# 6packRev1B.net
KiCad netlist of a schematic drawn in EAGLE
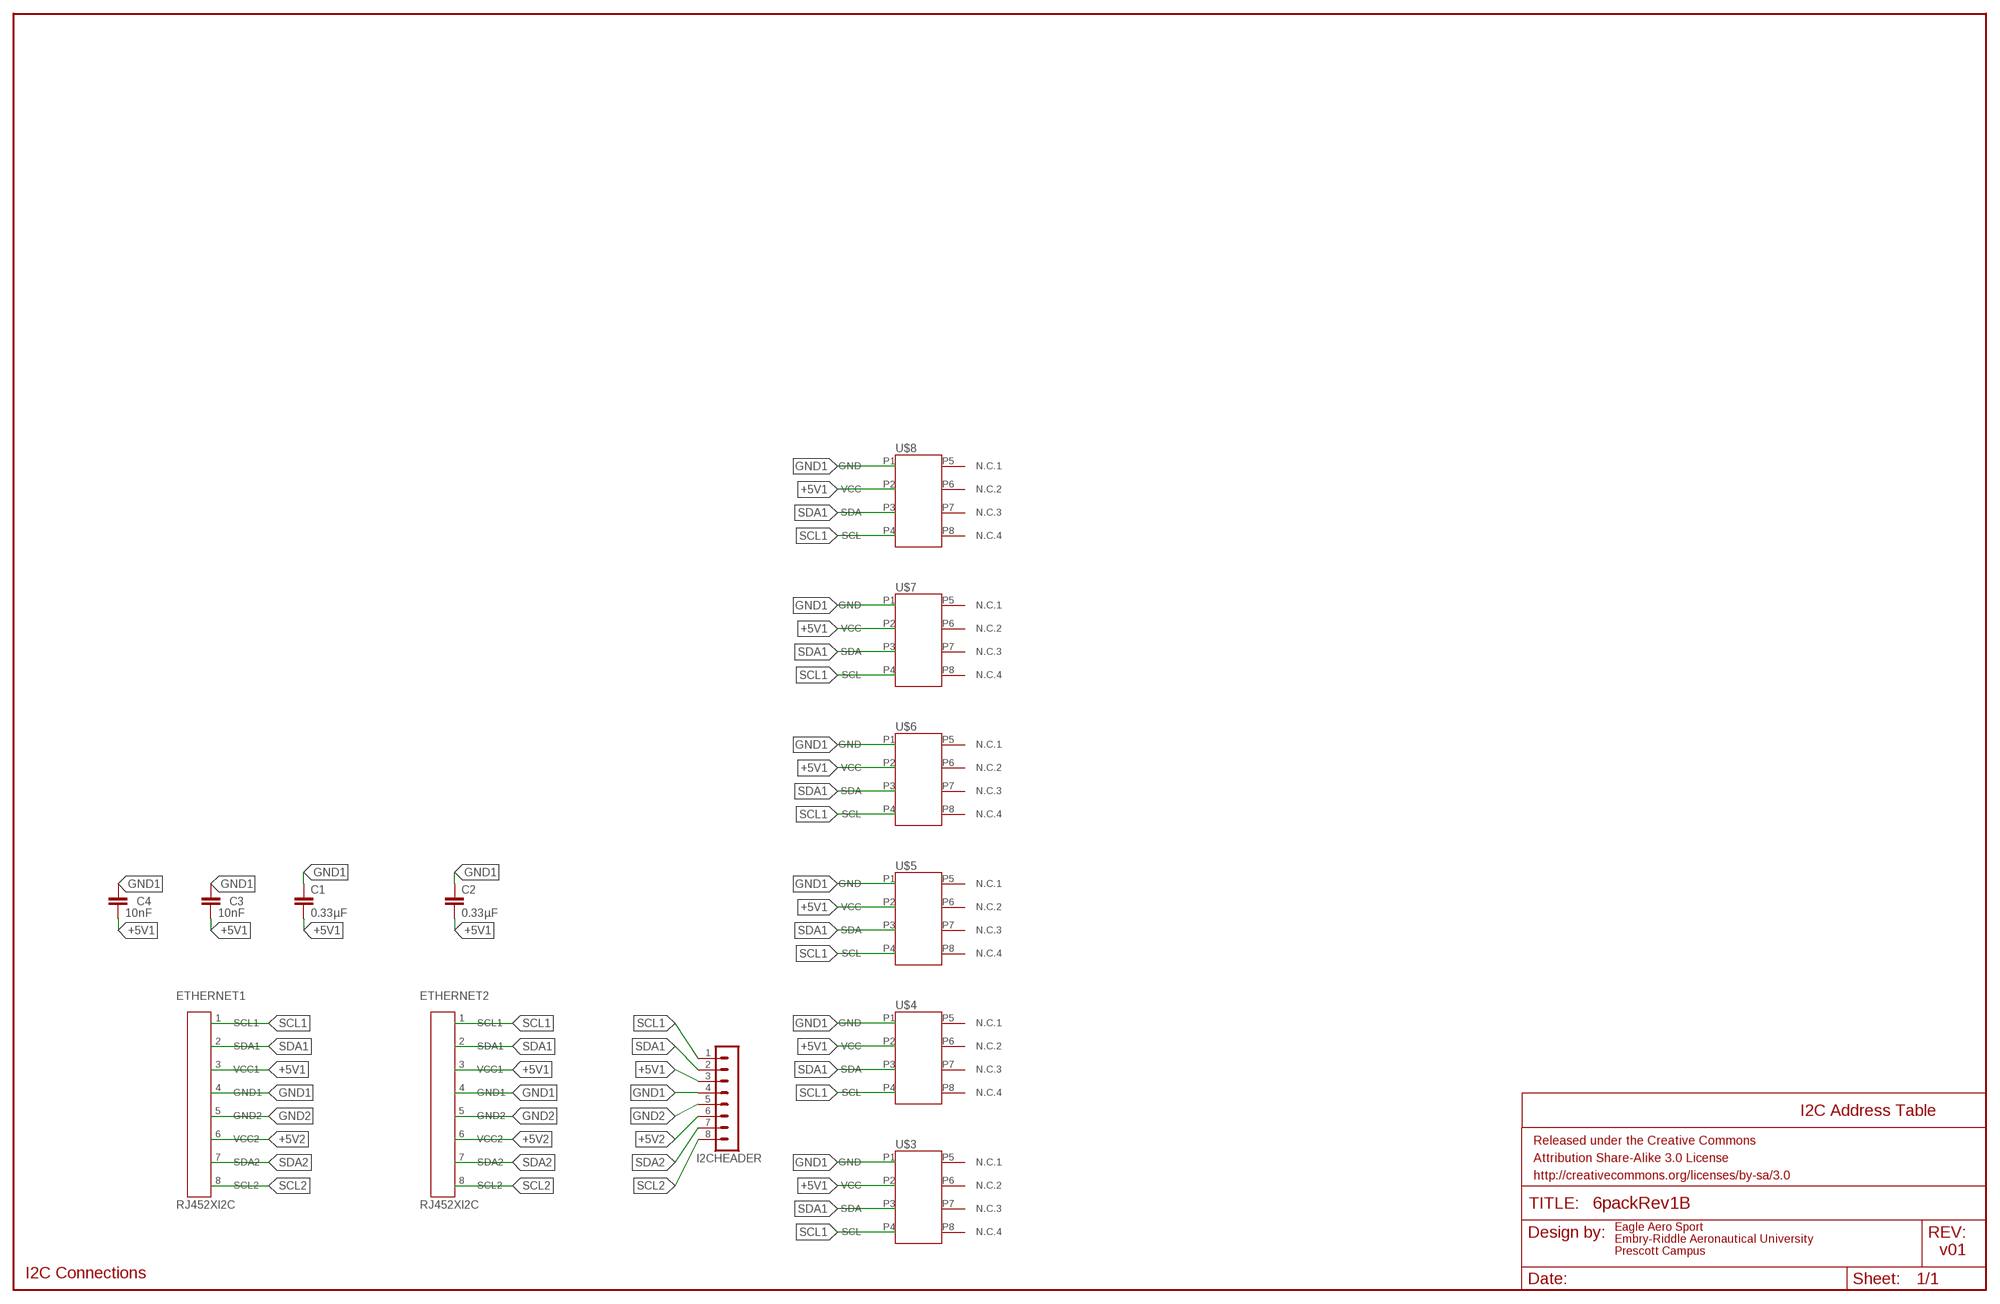
[diagram p0: schematic, sheet 1]

(export (version "E")
  (design (tool "Eeschema 10.0.6"))
  (components
    (comp (ref "C1")
      (value "0.33µF")
      (footprint "eagle-import:0805")
      (libsource (lib "eagle-import") (part "0.33UF/330NF-0805-50V-10%"))
    )
    (comp (ref "C2")
      (value "0.33µF")
      (footprint "eagle-import:0805")
      (libsource (lib "eagle-import") (part "0.33UF/330NF-0805-50V-10%"))
    )
    (comp (ref "C3")
      (value "10nF")
      (footprint "eagle-import:CAP-PTH-10MM")
      (libsource (lib "eagle-import") (part "10NF-PTH-10MM-10000V-1-%"))
    )
    (comp (ref "C4")
      (value "10nF")
      (footprint "eagle-import:CAP-PTH-10MM")
      (libsource (lib "eagle-import") (part "10NF-PTH-10MM-10000V-1-%"))
    )
    (comp (ref "ETHERNET1")
      (value "RJ452XI2C")
      (footprint "eagle-import:RJ45-8")
      (libsource (lib "eagle-import") (part "RJ452XI2C"))
    )
    (comp (ref "ETHERNET2")
      (value "RJ452XI2C")
      (footprint "eagle-import:RJ45-8")
      (libsource (lib "eagle-import") (part "RJ452XI2C"))
    )
    (comp (ref "FRAME1")
      (value "FRAME-LEDGER")
      (footprint "eagle-import:CREATIVE_COMMONS")
      (libsource (lib "eagle-import") (part "FRAME-LEDGER"))
    )
    (comp (ref "I2CHEADER")
      (value "MA08-1")
      (footprint "eagle-import:MA08-1")
      (libsource (lib "eagle-import") (part "MA08-1"))
    )
    (comp (ref "U$3")
      (value "AMS5915")
      (footprint "eagle-import:DIP8W")
      (libsource (lib "eagle-import") (part "AMS5915"))
    )
    (comp (ref "U$4")
      (value "AMS5915")
      (footprint "eagle-import:DIP8W")
      (libsource (lib "eagle-import") (part "AMS5915"))
    )
    (comp (ref "U$5")
      (value "AMS5915")
      (footprint "eagle-import:DIP8W")
      (libsource (lib "eagle-import") (part "AMS5915"))
    )
    (comp (ref "U$6")
      (value "AMS5915")
      (footprint "eagle-import:DIP8W")
      (libsource (lib "eagle-import") (part "AMS5915"))
    )
    (comp (ref "U$7")
      (value "AMS5915")
      (footprint "eagle-import:DIP8W")
      (libsource (lib "eagle-import") (part "AMS5915"))
    )
    (comp (ref "U$8")
      (value "AMS5915")
      (footprint "eagle-import:DIP8W")
      (libsource (lib "eagle-import") (part "AMS5915"))
    )
  )
  (nets
    (net (code "1") (name "+5V1") (class "Default")
      (node (ref "C1") (pin "2") (pinfunction "2_2") (pintype "passive"))
      (node (ref "C2") (pin "2") (pinfunction "2_2") (pintype "passive"))
      (node (ref "C3") (pin "2") (pinfunction "2_2") (pintype "passive"))
      (node (ref "C4") (pin "2") (pinfunction "2_2") (pintype "passive"))
      (node (ref "ETHERNET1") (pin "3") (pinfunction "VCC1_3") (pintype "bidirectional"))
      (node (ref "ETHERNET2") (pin "3") (pinfunction "VCC1_3") (pintype "bidirectional"))
      (node (ref "I2CHEADER") (pin "3") (pinfunction "3_3") (pintype "passive"))
      (node (ref "U$3") (pin "P2") (pinfunction "VCC_P2") (pintype "power_in"))
      (node (ref "U$4") (pin "P2") (pinfunction "VCC_P2") (pintype "power_in"))
      (node (ref "U$5") (pin "P2") (pinfunction "VCC_P2") (pintype "power_in"))
      (node (ref "U$6") (pin "P2") (pinfunction "VCC_P2") (pintype "power_in"))
      (node (ref "U$7") (pin "P2") (pinfunction "VCC_P2") (pintype "power_in"))
      (node (ref "U$8") (pin "P2") (pinfunction "VCC_P2") (pintype "power_in"))
    )
    (net (code "2") (name "+5V2") (class "Default")
      (node (ref "ETHERNET1") (pin "6") (pinfunction "VCC2_6") (pintype "bidirectional"))
      (node (ref "ETHERNET2") (pin "6") (pinfunction "VCC2_6") (pintype "bidirectional"))
      (node (ref "I2CHEADER") (pin "6") (pinfunction "6_6") (pintype "passive"))
    )
    (net (code "3") (name "GND1") (class "Default")
      (node (ref "C1") (pin "1") (pinfunction "1_1") (pintype "passive"))
      (node (ref "C2") (pin "1") (pinfunction "1_1") (pintype "passive"))
      (node (ref "C3") (pin "1") (pinfunction "1_1") (pintype "passive"))
      (node (ref "C4") (pin "1") (pinfunction "1_1") (pintype "passive"))
      (node (ref "ETHERNET1") (pin "4") (pinfunction "GND1_4") (pintype "bidirectional"))
      (node (ref "ETHERNET2") (pin "4") (pinfunction "GND1_4") (pintype "bidirectional"))
      (node (ref "I2CHEADER") (pin "4") (pinfunction "4_4") (pintype "passive"))
      (node (ref "U$3") (pin "P1") (pinfunction "GND_P1") (pintype "bidirectional"))
      (node (ref "U$4") (pin "P1") (pinfunction "GND_P1") (pintype "bidirectional"))
      (node (ref "U$5") (pin "P1") (pinfunction "GND_P1") (pintype "bidirectional"))
      (node (ref "U$6") (pin "P1") (pinfunction "GND_P1") (pintype "bidirectional"))
      (node (ref "U$7") (pin "P1") (pinfunction "GND_P1") (pintype "bidirectional"))
      (node (ref "U$8") (pin "P1") (pinfunction "GND_P1") (pintype "bidirectional"))
    )
    (net (code "4") (name "GND2") (class "Default")
      (node (ref "ETHERNET1") (pin "5") (pinfunction "GND2_5") (pintype "bidirectional"))
      (node (ref "ETHERNET2") (pin "5") (pinfunction "GND2_5") (pintype "bidirectional"))
      (node (ref "I2CHEADER") (pin "5") (pinfunction "5_5") (pintype "passive"))
    )
    (net (code "5") (name "SCL1") (class "Default")
      (node (ref "ETHERNET1") (pin "1") (pinfunction "SCL1_1") (pintype "bidirectional"))
      (node (ref "ETHERNET2") (pin "1") (pinfunction "SCL1_1") (pintype "bidirectional"))
      (node (ref "I2CHEADER") (pin "1") (pinfunction "1_1") (pintype "passive"))
      (node (ref "U$3") (pin "P4") (pinfunction "SCL_P4") (pintype "bidirectional"))
      (node (ref "U$4") (pin "P4") (pinfunction "SCL_P4") (pintype "bidirectional"))
      (node (ref "U$5") (pin "P4") (pinfunction "SCL_P4") (pintype "bidirectional"))
      (node (ref "U$6") (pin "P4") (pinfunction "SCL_P4") (pintype "bidirectional"))
      (node (ref "U$7") (pin "P4") (pinfunction "SCL_P4") (pintype "bidirectional"))
      (node (ref "U$8") (pin "P4") (pinfunction "SCL_P4") (pintype "bidirectional"))
    )
    (net (code "6") (name "SCL2") (class "Default")
      (node (ref "ETHERNET1") (pin "8") (pinfunction "SCL2_8") (pintype "bidirectional"))
      (node (ref "ETHERNET2") (pin "8") (pinfunction "SCL2_8") (pintype "bidirectional"))
      (node (ref "I2CHEADER") (pin "8") (pinfunction "8_8") (pintype "passive"))
    )
    (net (code "7") (name "SDA1") (class "Default")
      (node (ref "ETHERNET1") (pin "2") (pinfunction "SDA1_2") (pintype "bidirectional"))
      (node (ref "ETHERNET2") (pin "2") (pinfunction "SDA1_2") (pintype "bidirectional"))
      (node (ref "I2CHEADER") (pin "2") (pinfunction "2_2") (pintype "passive"))
      (node (ref "U$3") (pin "P3") (pinfunction "SDA_P3") (pintype "bidirectional"))
      (node (ref "U$4") (pin "P3") (pinfunction "SDA_P3") (pintype "bidirectional"))
      (node (ref "U$5") (pin "P3") (pinfunction "SDA_P3") (pintype "bidirectional"))
      (node (ref "U$6") (pin "P3") (pinfunction "SDA_P3") (pintype "bidirectional"))
      (node (ref "U$7") (pin "P3") (pinfunction "SDA_P3") (pintype "bidirectional"))
      (node (ref "U$8") (pin "P3") (pinfunction "SDA_P3") (pintype "bidirectional"))
    )
    (net (code "8") (name "SDA2") (class "Default")
      (node (ref "ETHERNET1") (pin "7") (pinfunction "SDA2_7") (pintype "bidirectional"))
      (node (ref "ETHERNET2") (pin "7") (pinfunction "SDA2_7") (pintype "bidirectional"))
      (node (ref "I2CHEADER") (pin "7") (pinfunction "7_7") (pintype "passive"))
    )
    (net (code "9") (name "unconnected-(U$3-N.C.1-PadP5)") (class "Default")
      (node (ref "U$3") (pin "P5") (pinfunction "N.C.1_P5") (pintype "no_connect"))
    )
    (net (code "10") (name "unconnected-(U$3-N.C.2-PadP6)") (class "Default")
      (node (ref "U$3") (pin "P6") (pinfunction "N.C.2_P6") (pintype "no_connect"))
    )
    (net (code "11") (name "unconnected-(U$3-N.C.3-PadP7)") (class "Default")
      (node (ref "U$3") (pin "P7") (pinfunction "N.C.3_P7") (pintype "no_connect"))
    )
    (net (code "12") (name "unconnected-(U$3-N.C.4-PadP8)") (class "Default")
      (node (ref "U$3") (pin "P8") (pinfunction "N.C.4_P8") (pintype "no_connect"))
    )
    (net (code "13") (name "unconnected-(U$4-N.C.1-PadP5)") (class "Default")
      (node (ref "U$4") (pin "P5") (pinfunction "N.C.1_P5") (pintype "no_connect"))
    )
    (net (code "14") (name "unconnected-(U$4-N.C.2-PadP6)") (class "Default")
      (node (ref "U$4") (pin "P6") (pinfunction "N.C.2_P6") (pintype "no_connect"))
    )
    (net (code "15") (name "unconnected-(U$4-N.C.3-PadP7)") (class "Default")
      (node (ref "U$4") (pin "P7") (pinfunction "N.C.3_P7") (pintype "no_connect"))
    )
    (net (code "16") (name "unconnected-(U$4-N.C.4-PadP8)") (class "Default")
      (node (ref "U$4") (pin "P8") (pinfunction "N.C.4_P8") (pintype "no_connect"))
    )
    (net (code "17") (name "unconnected-(U$5-N.C.1-PadP5)") (class "Default")
      (node (ref "U$5") (pin "P5") (pinfunction "N.C.1_P5") (pintype "no_connect"))
    )
    (net (code "18") (name "unconnected-(U$5-N.C.2-PadP6)") (class "Default")
      (node (ref "U$5") (pin "P6") (pinfunction "N.C.2_P6") (pintype "no_connect"))
    )
    (net (code "19") (name "unconnected-(U$5-N.C.3-PadP7)") (class "Default")
      (node (ref "U$5") (pin "P7") (pinfunction "N.C.3_P7") (pintype "no_connect"))
    )
    (net (code "20") (name "unconnected-(U$5-N.C.4-PadP8)") (class "Default")
      (node (ref "U$5") (pin "P8") (pinfunction "N.C.4_P8") (pintype "no_connect"))
    )
    (net (code "21") (name "unconnected-(U$6-N.C.1-PadP5)") (class "Default")
      (node (ref "U$6") (pin "P5") (pinfunction "N.C.1_P5") (pintype "no_connect"))
    )
    (net (code "22") (name "unconnected-(U$6-N.C.2-PadP6)") (class "Default")
      (node (ref "U$6") (pin "P6") (pinfunction "N.C.2_P6") (pintype "no_connect"))
    )
    (net (code "23") (name "unconnected-(U$6-N.C.3-PadP7)") (class "Default")
      (node (ref "U$6") (pin "P7") (pinfunction "N.C.3_P7") (pintype "no_connect"))
    )
    (net (code "24") (name "unconnected-(U$6-N.C.4-PadP8)") (class "Default")
      (node (ref "U$6") (pin "P8") (pinfunction "N.C.4_P8") (pintype "no_connect"))
    )
    (net (code "25") (name "unconnected-(U$7-N.C.1-PadP5)") (class "Default")
      (node (ref "U$7") (pin "P5") (pinfunction "N.C.1_P5") (pintype "no_connect"))
    )
    (net (code "26") (name "unconnected-(U$7-N.C.2-PadP6)") (class "Default")
      (node (ref "U$7") (pin "P6") (pinfunction "N.C.2_P6") (pintype "no_connect"))
    )
    (net (code "27") (name "unconnected-(U$7-N.C.3-PadP7)") (class "Default")
      (node (ref "U$7") (pin "P7") (pinfunction "N.C.3_P7") (pintype "no_connect"))
    )
    (net (code "28") (name "unconnected-(U$7-N.C.4-PadP8)") (class "Default")
      (node (ref "U$7") (pin "P8") (pinfunction "N.C.4_P8") (pintype "no_connect"))
    )
    (net (code "29") (name "unconnected-(U$8-N.C.1-PadP5)") (class "Default")
      (node (ref "U$8") (pin "P5") (pinfunction "N.C.1_P5") (pintype "no_connect"))
    )
    (net (code "30") (name "unconnected-(U$8-N.C.2-PadP6)") (class "Default")
      (node (ref "U$8") (pin "P6") (pinfunction "N.C.2_P6") (pintype "no_connect"))
    )
    (net (code "31") (name "unconnected-(U$8-N.C.3-PadP7)") (class "Default")
      (node (ref "U$8") (pin "P7") (pinfunction "N.C.3_P7") (pintype "no_connect"))
    )
    (net (code "32") (name "unconnected-(U$8-N.C.4-PadP8)") (class "Default")
      (node (ref "U$8") (pin "P8") (pinfunction "N.C.4_P8") (pintype "no_connect"))
    )
  )
)
